# Clap_sequence_light_switch.net
KiCad netlist of a schematic drawn in EasyEDA
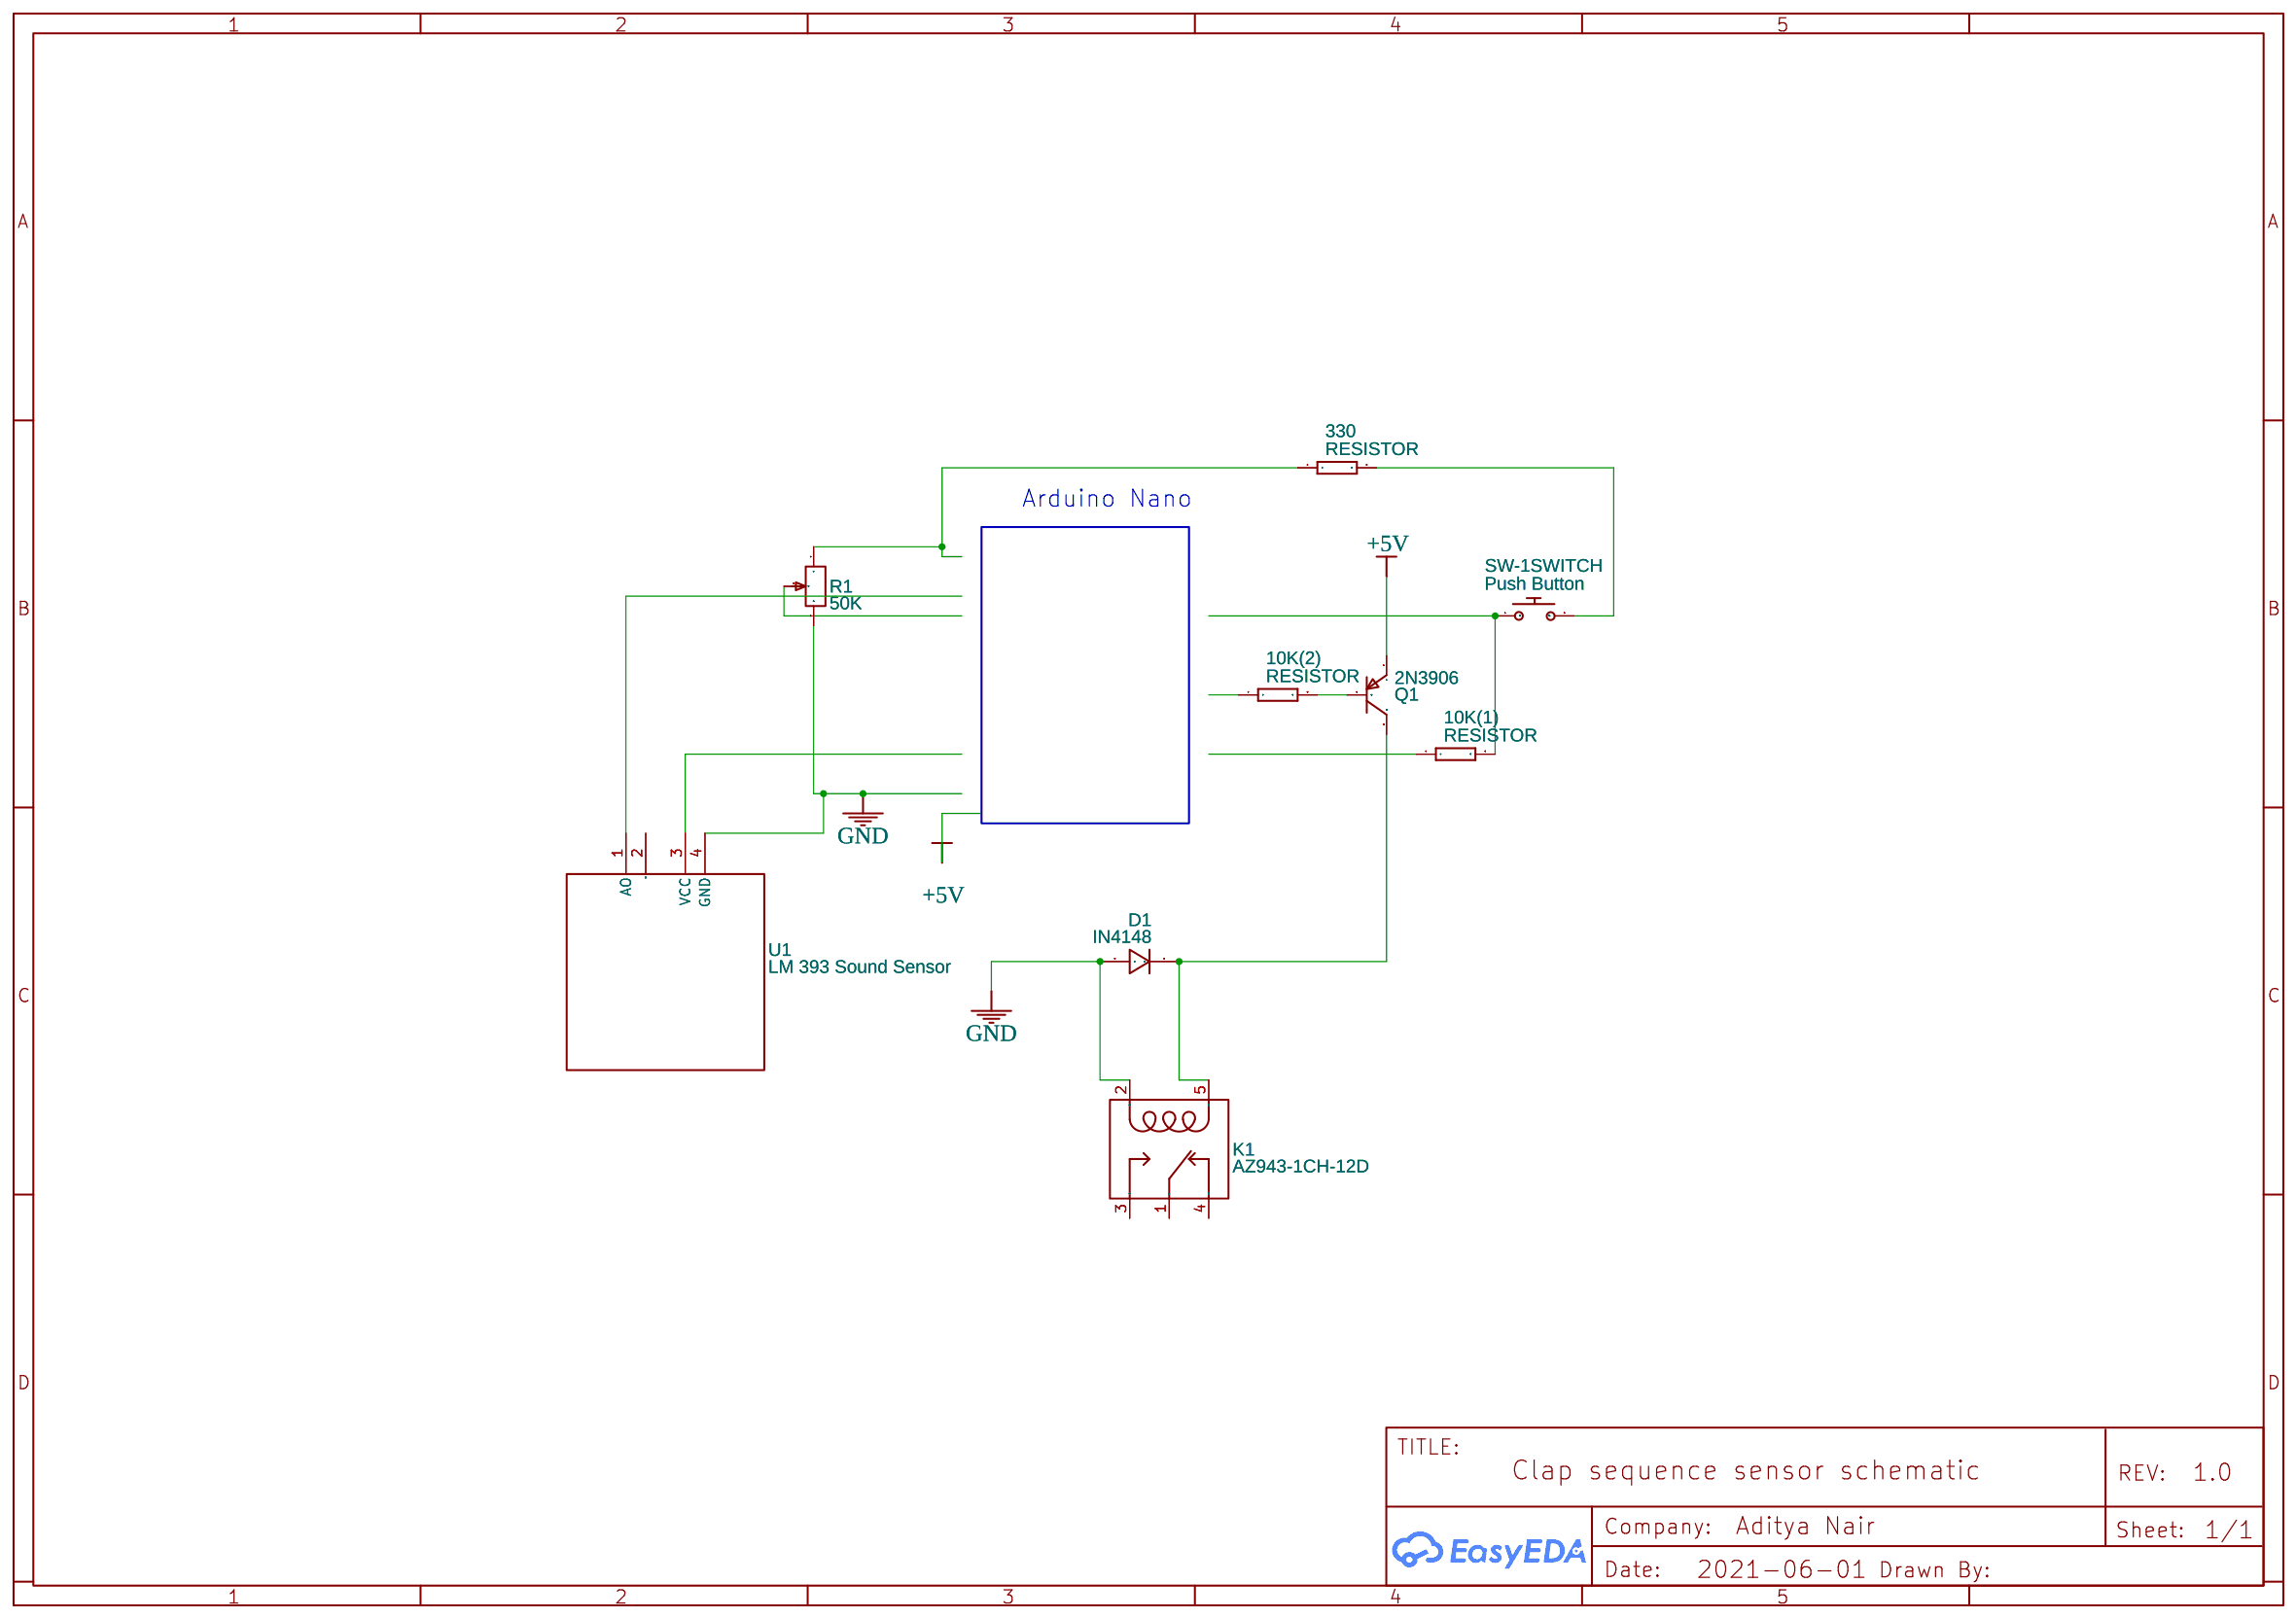
[diagram p0: schematic sheet]

(export (version "E")
  (design (tool "Eeschema 10.0.6"))
  (components
    (comp (ref "10K(1)") (value "RESISTOR") (libsource (lib "") (part "RESISTOR_2")))
    (comp (ref "10K(2)") (value "RESISTOR") (libsource (lib "") (part "RESISTOR")))
    (comp (ref "330") (value "RESISTOR") (libsource (lib "") (part "RESISTOR_1")))
    (comp (ref "D1")
      (value "IN4148")
      (fields (field (name "BOM_Supplier Part") "C14538"))
      (libsource (lib "") (part "IN4148"))
    )
    (comp (ref "K1")
      (value "AZ943-1CH-12D")
      (fields (field (name "BOM_Supplier Part") "C480616"))
      (libsource (lib "") (part "AZ943-1CH-12D"))
    )
    (comp (ref "Q1")
      (value "2N3906")
      (fields (field (name "BOM_Supplier Part") "C9809"))
      (libsource (lib "") (part "2N3906"))
    )
    (comp (ref "R1")
      (value "50K")
      (fields
        (field (name "BOM_Manufacturer Part") "RM063-503 50K")
        (field (name "BOM_Supplier Part") "C55977")
      )
      (libsource (lib "") (part "RM063-503 50K"))
    )
    (comp (ref "SW-1SWITCH")
      (value "Push Button")
      (fields (field (name "BOM_Supplier Part") "COM-08720"))
      (libsource (lib "") (part "Push Button"))
    )
    (comp (ref "U1")
      (value "LM 393 Sound Sensor")
      (fields (field (name "BOM_Supplier Part") "undefined"))
      (libsource (lib "") (part "Grove - Sound Sensor"))
    )
  )
  (nets
    (net (code "1") (name "+5V") (class "Default")
      (node (ref "Q1") (pin "1") (pinfunction "E_1") (pintype "unspecified"))
    )
    (net (code "2") (name "GND") (class "Default")
      (node (ref "D1") (pin "2") (pinfunction "2_2") (pintype "unspecified"))
      (node (ref "K1") (pin "2") (pinfunction "COIL2_2") (pintype "unspecified"))
      (node (ref "R1") (pin "3") (pinfunction "3_3") (pintype "input"))
      (node (ref "U1") (pin "4") (pinfunction "GND_4") (pintype "unspecified"))
    )
    (net (code "3") (name "Net-(330-Pad1)") (class "Default")
      (node (ref "330") (pin "1") (pinfunction "1_1") (pintype "unspecified"))
      (node (ref "R1") (pin "1") (pinfunction "1_1") (pintype "input"))
    )
    (net (code "4") (name "Net-(K1-COIL1)") (class "Default")
      (node (ref "D1") (pin "1") (pinfunction "1_1") (pintype "unspecified"))
      (node (ref "K1") (pin "5") (pinfunction "COIL1_5") (pintype "unspecified"))
      (node (ref "Q1") (pin "3") (pinfunction "C_3") (pintype "unspecified"))
    )
    (net (code "5") (name "Net-(Q1-B)") (class "Default")
      (node (ref "10K(2)") (pin "2") (pinfunction "2_2") (pintype "unspecified"))
      (node (ref "Q1") (pin "2") (pinfunction "B_2") (pintype "unspecified"))
    )
    (net (code "6") (name "Net-(SW-1SWITCH-P$1)") (class "Default")
      (node (ref "10K(1)") (pin "2") (pinfunction "2_2") (pintype "unspecified"))
      (node (ref "SW-1SWITCH") (pin "1") (pinfunction "P$1_1") (pintype "unspecified"))
    )
    (net (code "7") (name "Net-(SW-1SWITCH-P$2)") (class "Default")
      (node (ref "330") (pin "2") (pinfunction "2_2") (pintype "unspecified"))
      (node (ref "SW-1SWITCH") (pin "2") (pinfunction "P$2_2") (pintype "unspecified"))
    )
    (net (code "8") (name "unconnected-(10K(1)-Pad1)") (class "Default")
      (node (ref "10K(1)") (pin "1") (pinfunction "1_1") (pintype "unspecified"))
    )
    (net (code "9") (name "unconnected-(10K(2)-Pad1)") (class "Default")
      (node (ref "10K(2)") (pin "1") (pinfunction "1_1") (pintype "unspecified"))
    )
    (net (code "10") (name "unconnected-(K1-C-Pad1)") (class "Default")
      (node (ref "K1") (pin "1") (pinfunction "C_1") (pintype "unspecified"))
    )
    (net (code "11") (name "unconnected-(K1-NC-Pad4)") (class "Default")
      (node (ref "K1") (pin "4") (pinfunction "NC_4") (pintype "unspecified"))
    )
    (net (code "12") (name "unconnected-(K1-NO-Pad3)") (class "Default")
      (node (ref "K1") (pin "3") (pinfunction "NO_3") (pintype "unspecified"))
    )
    (net (code "13") (name "unconnected-(R1-Pad2)") (class "Default")
      (node (ref "R1") (pin "2") (pinfunction "2_2") (pintype "input"))
    )
    (net (code "14") (name "unconnected-(U1-AO-Pad1)") (class "Default")
      (node (ref "U1") (pin "1") (pinfunction "AO_1") (pintype "unspecified"))
    )
    (net (code "15") (name "unconnected-(U1-NC-Pad2)") (class "Default")
      (node (ref "U1") (pin "2") (pinfunction "NC_2") (pintype "unspecified"))
    )
    (net (code "16") (name "unconnected-(U1-VCC-Pad3)") (class "Default")
      (node (ref "U1") (pin "3") (pinfunction "VCC_3") (pintype "unspecified"))
    )
  )
)
